# sensor_v15.net
KiCad netlist of a schematic drawn in EAGLE
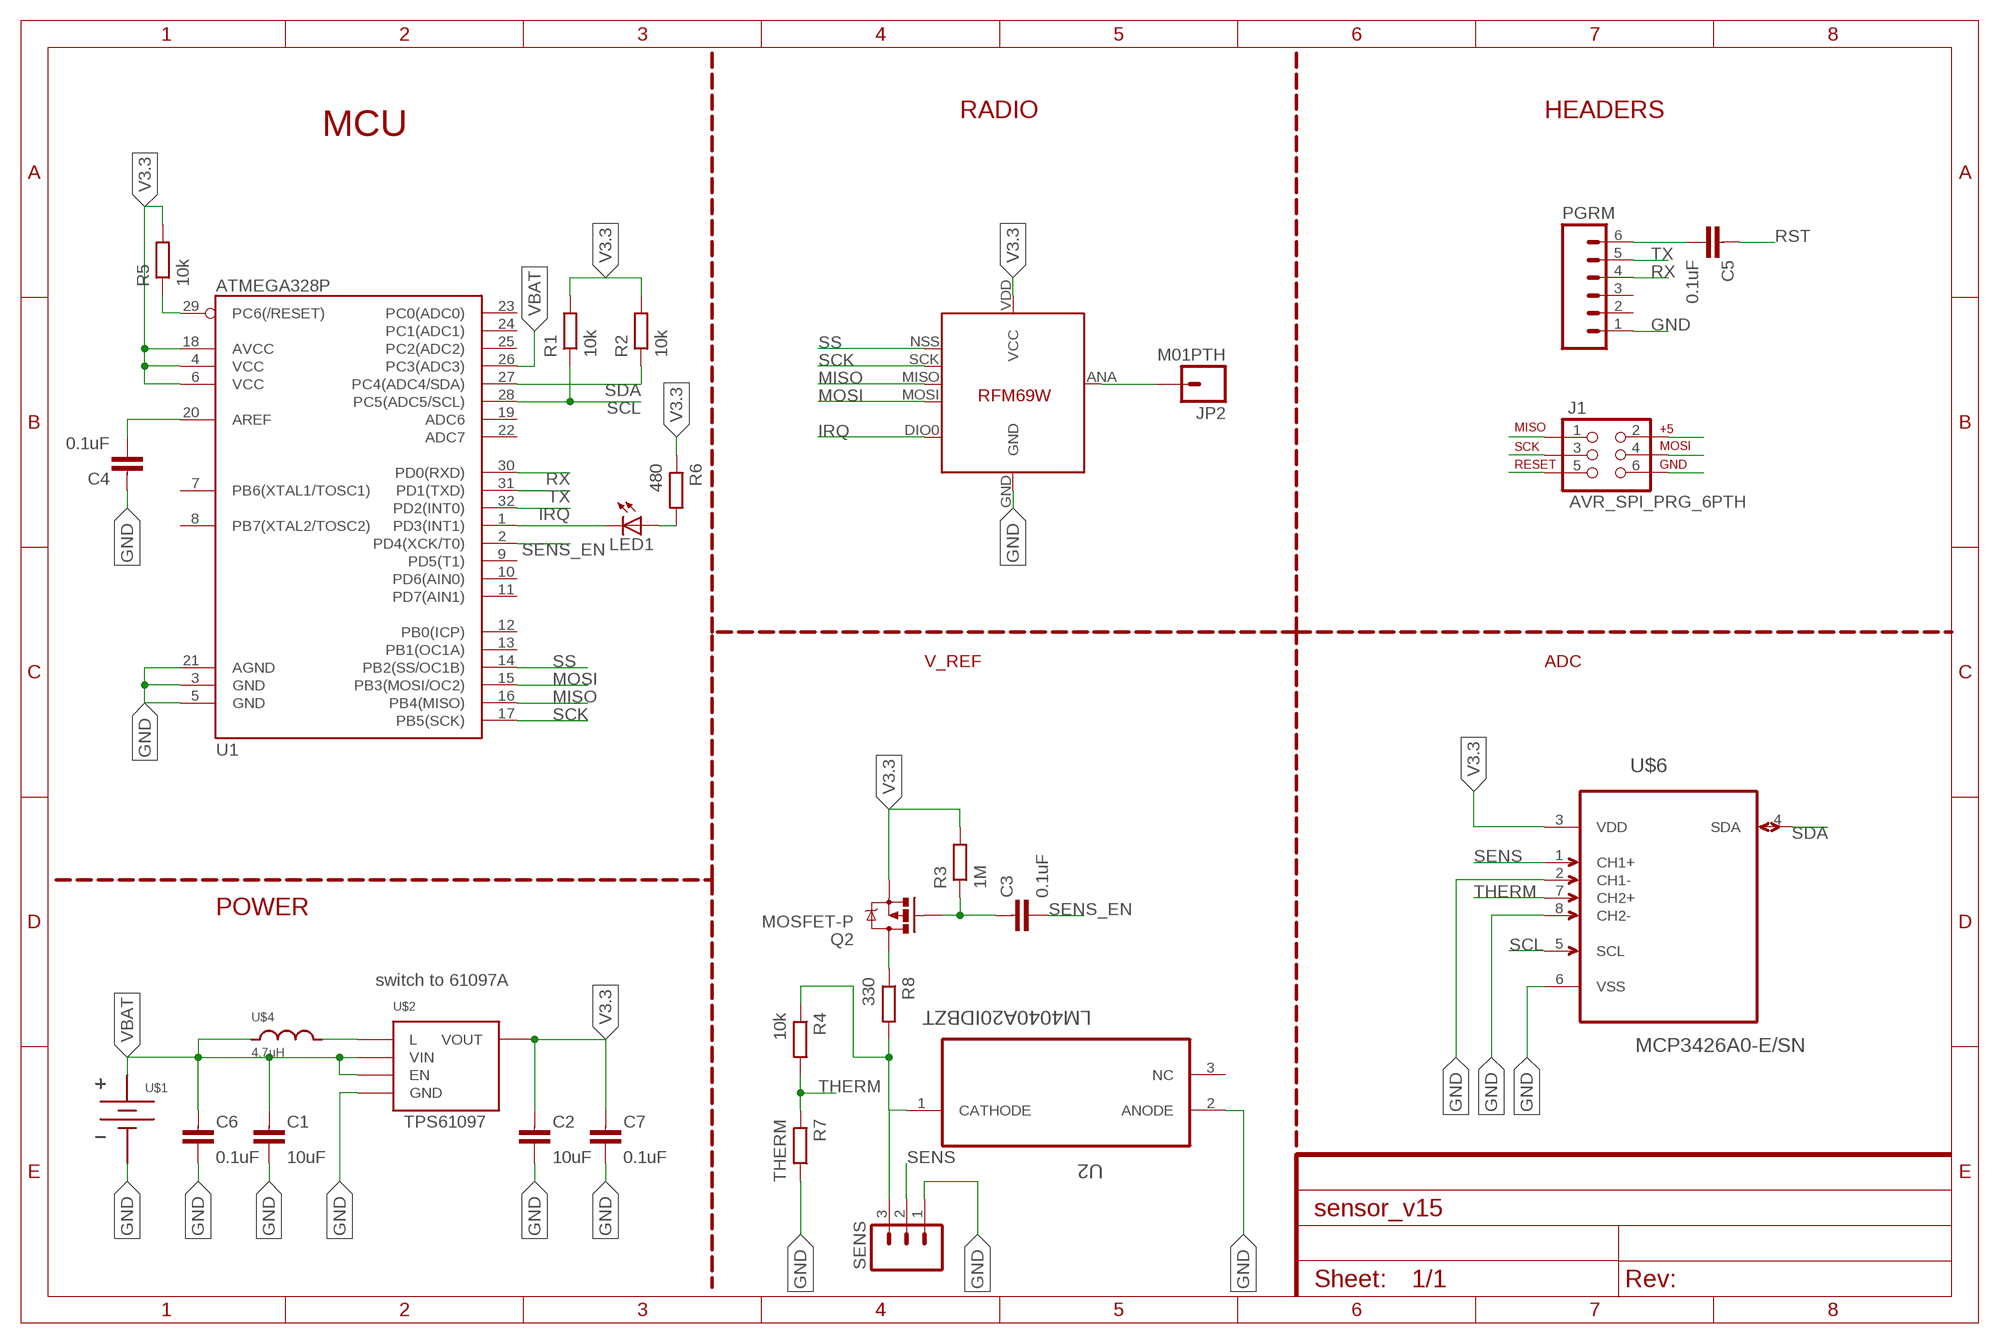
[diagram p0: schematic, sheet 1]

(export (version "E")
  (design (tool "Eeschema 10.0.6"))
  (components
    (comp (ref "C1")
      (value "10uF")
      (footprint "eagle-import:C0805-N")
      (libsource (lib "eagle-import") (part "CAPACITOR0805-N"))
    )
    (comp (ref "C2")
      (value "10uF")
      (footprint "eagle-import:C0805-N")
      (libsource (lib "eagle-import") (part "CAPACITOR0805-N"))
    )
    (comp (ref "C3")
      (value "0.1uF")
      (footprint "eagle-import:C0603-N")
      (libsource (lib "eagle-import") (part "CAPACITOR0603-N"))
    )
    (comp (ref "C4")
      (value "0.1uF")
      (footprint "eagle-import:C0603-N")
      (libsource (lib "eagle-import") (part "CAPACITOR0603-N"))
    )
    (comp (ref "C5")
      (value "0.1uF")
      (footprint "eagle-import:C0603-N")
      (libsource (lib "eagle-import") (part "CAPACITOR0603-N"))
    )
    (comp (ref "C6")
      (value "0.1uF")
      (footprint "eagle-import:C0603-N")
      (libsource (lib "eagle-import") (part "CAPACITOR0603-N"))
    )
    (comp (ref "C7")
      (value "0.1uF")
      (footprint "eagle-import:C0603-N")
      (libsource (lib "eagle-import") (part "CAPACITOR0603-N"))
    )
    (comp (ref "J1")
      (value "AVR_SPI_PRG_6PTH")
      (footprint "eagle-import:2X3")
      (libsource (lib "eagle-import") (part "AVR_SPI_PRG_6PTH"))
    )
    (comp (ref "JP2")
      (value "M01PTH")
      (footprint "eagle-import:1X01")
      (libsource (lib "eagle-import") (part "M01PTH"))
    )
    (comp (ref "LED1")
      (value "LED0603")
      (footprint "eagle-import:LED-0603")
      (libsource (lib "eagle-import") (part "LED0603"))
    )
    (comp (ref "PGRM")
      (value "M06LONGPADS")
      (footprint "eagle-import:1X06_LONGPADS")
      (libsource (lib "eagle-import") (part "M06LONGPADS"))
    )
    (comp (ref "Q2")
      (value "MOSFET-P")
      (footprint "eagle-import:SOT23-3")
      (libsource (lib "eagle-import") (part "MOSFET-PCHANNELIRLML2244"))
    )
    (comp (ref "R1")
      (value "10k")
      (footprint "eagle-import:R0603-N")
      (libsource (lib "eagle-import") (part "RESISTOR0603-N"))
    )
    (comp (ref "R2")
      (value "10k")
      (footprint "eagle-import:R0603-N")
      (libsource (lib "eagle-import") (part "RESISTOR0603-N"))
    )
    (comp (ref "R3")
      (value "1M")
      (footprint "eagle-import:R0603-N")
      (libsource (lib "eagle-import") (part "RESISTOR0603-N"))
    )
    (comp (ref "R4")
      (value "10k")
      (footprint "eagle-import:R0603-N")
      (libsource (lib "eagle-import") (part "RESISTOR0603-N"))
    )
    (comp (ref "R5")
      (value "10k")
      (footprint "eagle-import:R0603-N")
      (libsource (lib "eagle-import") (part "RESISTOR0603-N"))
    )
    (comp (ref "R6")
      (value "480")
      (footprint "eagle-import:R0603-N")
      (libsource (lib "eagle-import") (part "RESISTOR0603-N"))
    )
    (comp (ref "R7")
      (value "THERM")
      (footprint "eagle-import:R0603-N")
      (libsource (lib "eagle-import") (part "RESISTOR0603-N"))
    )
    (comp (ref "R8")
      (value "330")
      (footprint "eagle-import:R0603-N")
      (libsource (lib "eagle-import") (part "RESISTOR0603-N"))
    )
    (comp (ref "SENS")
      (value "M03PTH")
      (footprint "eagle-import:1X03")
      (libsource (lib "eagle-import") (part "M03PTH"))
    )
    (comp (ref "U$1")
      (value "KEYSTONEAAHOLDER_2CELL")
      (footprint "eagle-import:KEYSTONEAAHOLDER_2CELL")
      (libsource (lib "eagle-import") (part "KEYSTONEAAHOLDER_2CELL"))
    )
    (comp (ref "U$2")
      (value "TPS61097-33")
      (footprint "eagle-import:SOT23-5")
      (libsource (lib "eagle-import") (part "TPS61097-33"))
    )
    (comp (ref "U$4")
      (value "4.7uH")
      (footprint "eagle-import:WURTH_10UH_650MA")
      (libsource (lib "eagle-import") (part "INDUCTORS_WURTH"))
    )
    (comp (ref "U$5")
      (value "RFM69")
      (footprint "eagle-import:RFM69W-MINPADS")
      (libsource (lib "eagle-import") (part "RFM69"))
    )
    (comp (ref "U$6")
      (value "MCP3426A0-E/SN")
      (footprint "eagle-import:SOIC127P600X175-8N")
      (libsource (lib "eagle-import") (part "MCP3426A0-E/SN"))
    )
    (comp (ref "U1")
      (value "ATMEGA328P")
      (footprint "eagle-import:TQFP32-08")
      (libsource (lib "eagle-import") (part "ATMEGA328_SMT"))
    )
    (comp (ref "U2")
      (value "LM4040A20IDBZT")
      (footprint "eagle-import:SOT95P237X112-3N")
      (libsource (lib "eagle-import") (part "LM4040A20IDBZT"))
    )
  )
  (nets
    (net (code "1") (name "/IRQ") (class "Default")
      (node (ref "U$5") (pin "DIO0") (pinfunction "DIO0_DIO0") (pintype "open_collector"))
      (node (ref "U1") (pin "32") (pinfunction "PD2(INT0)_32") (pintype "bidirectional"))
    )
    (net (code "2") (name "/MISO") (class "Default")
      (node (ref "J1") (pin "1") (pinfunction "1_1") (pintype "passive"))
      (node (ref "U$5") (pin "MISO") (pinfunction "MISO_MISO") (pintype "input"))
      (node (ref "U1") (pin "16") (pinfunction "PB4(MISO)_16") (pintype "bidirectional"))
    )
    (net (code "3") (name "/MOSI") (class "Default")
      (node (ref "J1") (pin "4") (pinfunction "4_4") (pintype "passive"))
      (node (ref "U$5") (pin "MOSI") (pinfunction "MOSI_MOSI") (pintype "output"))
      (node (ref "U1") (pin "15") (pinfunction "PB3(MOSI/OC2)_15") (pintype "bidirectional"))
    )
    (net (code "4") (name "/RST") (class "Default")
      (node (ref "C5") (pin "1") (pinfunction "1_1") (pintype "passive"))
      (node (ref "J1") (pin "5") (pinfunction "5_5") (pintype "passive"))
      (node (ref "R5") (pin "1") (pinfunction "P$1_1") (pintype "passive"))
      (node (ref "U1") (pin "29") (pinfunction "PC6(/RESET)_29") (pintype "bidirectional"))
    )
    (net (code "5") (name "/RX") (class "Default")
      (node (ref "PGRM") (pin "4") (pinfunction "4_4") (pintype "passive"))
      (node (ref "U1") (pin "30") (pinfunction "PD0(RXD)_30") (pintype "bidirectional"))
    )
    (net (code "6") (name "/SCK") (class "Default")
      (node (ref "J1") (pin "3") (pinfunction "3_3") (pintype "passive"))
      (node (ref "U$5") (pin "SCK") (pinfunction "SCK_SCK") (pintype "input"))
      (node (ref "U1") (pin "17") (pinfunction "PB5(SCK)_17") (pintype "bidirectional"))
    )
    (net (code "7") (name "/SCL") (class "Default")
      (node (ref "R1") (pin "1") (pinfunction "P$1_1") (pintype "passive"))
      (node (ref "U$6") (pin "5") (pinfunction "SCL_5") (pintype "input"))
      (node (ref "U1") (pin "28") (pinfunction "PC5(ADC5/SCL)_28") (pintype "bidirectional"))
    )
    (net (code "8") (name "/SDA") (class "Default")
      (node (ref "R2") (pin "1") (pinfunction "P$1_1") (pintype "passive"))
      (node (ref "U$6") (pin "4") (pinfunction "SDA_4") (pintype "bidirectional"))
      (node (ref "U1") (pin "27") (pinfunction "PC4(ADC4/SDA)_27") (pintype "bidirectional"))
    )
    (net (code "9") (name "/SENS") (class "Default")
      (node (ref "SENS") (pin "2") (pinfunction "2_2") (pintype "passive"))
      (node (ref "U$6") (pin "1") (pinfunction "CH1+_1") (pintype "input"))
    )
    (net (code "10") (name "/SENS_EN") (class "Default")
      (node (ref "C3") (pin "2") (pinfunction "2_2") (pintype "passive"))
      (node (ref "U1") (pin "2") (pinfunction "PD4(XCK/T0)_2") (pintype "bidirectional"))
    )
    (net (code "11") (name "/SS") (class "Default")
      (node (ref "U$5") (pin "NSS") (pinfunction "SEL_NSS") (pintype "input"))
      (node (ref "U1") (pin "14") (pinfunction "PB2(SS/OC1B)_14") (pintype "bidirectional"))
    )
    (net (code "12") (name "/THERM") (class "Default")
      (node (ref "R4") (pin "2") (pinfunction "P$2_2") (pintype "passive"))
      (node (ref "R7") (pin "1") (pinfunction "P$1_1") (pintype "passive"))
      (node (ref "U$6") (pin "7") (pinfunction "CH2+_7") (pintype "input"))
    )
    (net (code "13") (name "/TX") (class "Default")
      (node (ref "PGRM") (pin "5") (pinfunction "5_5") (pintype "passive"))
      (node (ref "U1") (pin "31") (pinfunction "PD1(TXD)_31") (pintype "bidirectional"))
    )
    (net (code "14") (name "GND") (class "Default")
      (node (ref "C1") (pin "2") (pinfunction "2_2") (pintype "passive"))
      (node (ref "C2") (pin "2") (pinfunction "2_2") (pintype "passive"))
      (node (ref "C4") (pin "1") (pinfunction "1_1") (pintype "passive"))
      (node (ref "C6") (pin "2") (pinfunction "2_2") (pintype "passive"))
      (node (ref "C7") (pin "2") (pinfunction "2_2") (pintype "passive"))
      (node (ref "J1") (pin "6") (pinfunction "6_6") (pintype "passive"))
      (node (ref "PGRM") (pin "1") (pinfunction "1_1") (pintype "passive"))
      (node (ref "R7") (pin "2") (pinfunction "P$2_2") (pintype "passive"))
      (node (ref "SENS") (pin "1") (pinfunction "1_1") (pintype "passive"))
      (node (ref "U$1") (pin "P$2") (pinfunction "GND_P$2") (pintype "bidirectional"))
      (node (ref "U$2") (pin "P$2") (pinfunction "GND_P$2") (pintype "power_in"))
      (node (ref "U$5") (pin "GND") (pinfunction "GND_GND") (pintype "power_in"))
      (node (ref "U$6") (pin "2") (pinfunction "CH1-_2") (pintype "input"))
      (node (ref "U$6") (pin "6") (pinfunction "VSS_6") (pintype "power_in"))
      (node (ref "U$6") (pin "8") (pinfunction "CH2-_8") (pintype "input"))
      (node (ref "U1") (pin "21") (pinfunction "AGND_21") (pintype "bidirectional"))
      (node (ref "U1") (pin "3") (pinfunction "GND_3") (pintype "bidirectional"))
      (node (ref "U1") (pin "5") (pinfunction "GND_5") (pintype "bidirectional"))
      (node (ref "U2") (pin "2") (pinfunction "ANODE_2") (pintype "input"))
    )
    (net (code "15") (name "Net-(C5-Pad2)") (class "Default")
      (node (ref "C5") (pin "2") (pinfunction "2_2") (pintype "passive"))
      (node (ref "PGRM") (pin "6") (pinfunction "6_6") (pintype "passive"))
    )
    (net (code "16") (name "Net-(Q2-D)") (class "Default")
      (node (ref "Q2") (pin "3") (pinfunction "D_3") (pintype "passive"))
      (node (ref "R8") (pin "1") (pinfunction "P$1_1") (pintype "passive"))
    )
    (net (code "17") (name "Net-(Q2-G)") (class "Default")
      (node (ref "C3") (pin "1") (pinfunction "1_1") (pintype "passive"))
      (node (ref "Q2") (pin "1") (pinfunction "G_1") (pintype "passive"))
      (node (ref "R3") (pin "1") (pinfunction "P$1_1") (pintype "passive"))
    )
    (net (code "18") (name "Net-(R4-P$1)") (class "Default")
      (node (ref "R4") (pin "1") (pinfunction "P$1_1") (pintype "passive"))
      (node (ref "R8") (pin "2") (pinfunction "P$2_2") (pintype "passive"))
      (node (ref "SENS") (pin "3") (pinfunction "3_3") (pintype "passive"))
      (node (ref "U2") (pin "1") (pinfunction "CATHODE_1") (pintype "output"))
    )
    (net (code "19") (name "Net-(R6-P$2)") (class "Default")
      (node (ref "LED1") (pin "A") (pinfunction "A_A") (pintype "passive"))
      (node (ref "R6") (pin "2") (pinfunction "P$2_2") (pintype "passive"))
    )
    (net (code "20") (name "Net-(U$2-L)") (class "Default")
      (node (ref "U$2") (pin "P$5") (pinfunction "L_P$5") (pintype "bidirectional"))
      (node (ref "U$4") (pin "P$1") (pinfunction "P$1_P$1") (pintype "passive"))
    )
    (net (code "21") (name "Net-(U$5-ANT)") (class "Default")
      (node (ref "JP2") (pin "1") (pinfunction "1_1") (pintype "passive"))
      (node (ref "U$5") (pin "ANA") (pinfunction "ANT_ANA") (pintype "passive"))
    )
    (net (code "22") (name "Net-(U1-AREF)") (class "Default")
      (node (ref "C4") (pin "2") (pinfunction "2_2") (pintype "passive"))
      (node (ref "U1") (pin "20") (pinfunction "AREF_20") (pintype "bidirectional"))
    )
    (net (code "23") (name "Net-(U1-PD3(INT1))") (class "Default")
      (node (ref "LED1") (pin "C") (pinfunction "C_C") (pintype "passive"))
      (node (ref "U1") (pin "1") (pinfunction "PD3(INT1)_1") (pintype "bidirectional"))
    )
    (net (code "24") (name "V3.3") (class "Default")
      (node (ref "C2") (pin "1") (pinfunction "1_1") (pintype "passive"))
      (node (ref "C7") (pin "1") (pinfunction "1_1") (pintype "passive"))
      (node (ref "J1") (pin "2") (pinfunction "2_2") (pintype "passive"))
      (node (ref "Q2") (pin "2") (pinfunction "S_2") (pintype "passive"))
      (node (ref "R1") (pin "2") (pinfunction "P$2_2") (pintype "passive"))
      (node (ref "R2") (pin "2") (pinfunction "P$2_2") (pintype "passive"))
      (node (ref "R3") (pin "2") (pinfunction "P$2_2") (pintype "passive"))
      (node (ref "R5") (pin "2") (pinfunction "P$2_2") (pintype "passive"))
      (node (ref "R6") (pin "1") (pinfunction "P$1_1") (pintype "passive"))
      (node (ref "U$2") (pin "P$4") (pinfunction "VOUT_P$4") (pintype "power_in"))
      (node (ref "U$5") (pin "VDD") (pinfunction "VCC_VDD") (pintype "power_in"))
      (node (ref "U$6") (pin "3") (pinfunction "VDD_3") (pintype "power_in"))
      (node (ref "U1") (pin "18") (pinfunction "AVCC_18") (pintype "bidirectional"))
      (node (ref "U1") (pin "4") (pinfunction "VCC_4") (pintype "bidirectional"))
      (node (ref "U1") (pin "6") (pinfunction "VCC_6") (pintype "bidirectional"))
    )
    (net (code "25") (name "VBAT") (class "Default")
      (node (ref "C1") (pin "1") (pinfunction "1_1") (pintype "passive"))
      (node (ref "C6") (pin "1") (pinfunction "1_1") (pintype "passive"))
      (node (ref "U$1") (pin "P$1") (pinfunction "VBAT_P$1") (pintype "bidirectional"))
      (node (ref "U$2") (pin "P$1") (pinfunction "VIN_P$1") (pintype "power_in"))
      (node (ref "U$2") (pin "P$3") (pinfunction "EN_P$3") (pintype "bidirectional"))
      (node (ref "U$4") (pin "P$2") (pinfunction "P$2_P$2") (pintype "passive"))
      (node (ref "U1") (pin "26") (pinfunction "PC3(ADC3)_26") (pintype "bidirectional"))
    )
    (net (code "26") (name "unconnected-(PGRM-Pad2)") (class "Default")
      (node (ref "PGRM") (pin "2") (pinfunction "2_2") (pintype "passive"))
    )
    (net (code "27") (name "unconnected-(PGRM-Pad3)") (class "Default")
      (node (ref "PGRM") (pin "3") (pinfunction "3_3") (pintype "passive"))
    )
    (net (code "28") (name "unconnected-(U1-ADC6-Pad19)") (class "Default")
      (node (ref "U1") (pin "19") (pinfunction "ADC6_19") (pintype "bidirectional"))
    )
    (net (code "29") (name "unconnected-(U1-ADC7-Pad22)") (class "Default")
      (node (ref "U1") (pin "22") (pinfunction "ADC7_22") (pintype "bidirectional"))
    )
    (net (code "30") (name "unconnected-(U1-PB0(ICP)-Pad12)") (class "Default")
      (node (ref "U1") (pin "12") (pinfunction "PB0(ICP)_12") (pintype "bidirectional"))
    )
    (net (code "31") (name "unconnected-(U1-PB1(OC1A)-Pad13)") (class "Default")
      (node (ref "U1") (pin "13") (pinfunction "PB1(OC1A)_13") (pintype "bidirectional"))
    )
    (net (code "32") (name "unconnected-(U1-PB6(XTAL1{slash}TOSC1)-Pad7)") (class "Default")
      (node (ref "U1") (pin "7") (pinfunction "PB6(XTAL1/TOSC1)_7") (pintype "bidirectional"))
    )
    (net (code "33") (name "unconnected-(U1-PB7(XTAL2{slash}TOSC2)-Pad8)") (class "Default")
      (node (ref "U1") (pin "8") (pinfunction "PB7(XTAL2/TOSC2)_8") (pintype "bidirectional"))
    )
    (net (code "34") (name "unconnected-(U1-PC0(ADC0)-Pad23)") (class "Default")
      (node (ref "U1") (pin "23") (pinfunction "PC0(ADC0)_23") (pintype "bidirectional"))
    )
    (net (code "35") (name "unconnected-(U1-PC1(ADC1)-Pad24)") (class "Default")
      (node (ref "U1") (pin "24") (pinfunction "PC1(ADC1)_24") (pintype "bidirectional"))
    )
    (net (code "36") (name "unconnected-(U1-PC2(ADC2)-Pad25)") (class "Default")
      (node (ref "U1") (pin "25") (pinfunction "PC2(ADC2)_25") (pintype "bidirectional"))
    )
    (net (code "37") (name "unconnected-(U1-PD5(T1)-Pad9)") (class "Default")
      (node (ref "U1") (pin "9") (pinfunction "PD5(T1)_9") (pintype "bidirectional"))
    )
    (net (code "38") (name "unconnected-(U1-PD6(AIN0)-Pad10)") (class "Default")
      (node (ref "U1") (pin "10") (pinfunction "PD6(AIN0)_10") (pintype "bidirectional"))
    )
    (net (code "39") (name "unconnected-(U1-PD7(AIN1)-Pad11)") (class "Default")
      (node (ref "U1") (pin "11") (pinfunction "PD7(AIN1)_11") (pintype "bidirectional"))
    )
    (net (code "40") (name "unconnected-(U2-NC-Pad3)") (class "Default")
      (node (ref "U2") (pin "3") (pinfunction "NC_3") (pintype "no_connect"))
    )
  )
)
